# SFP.net
KiCad netlist of a schematic drawn in Altium Designer
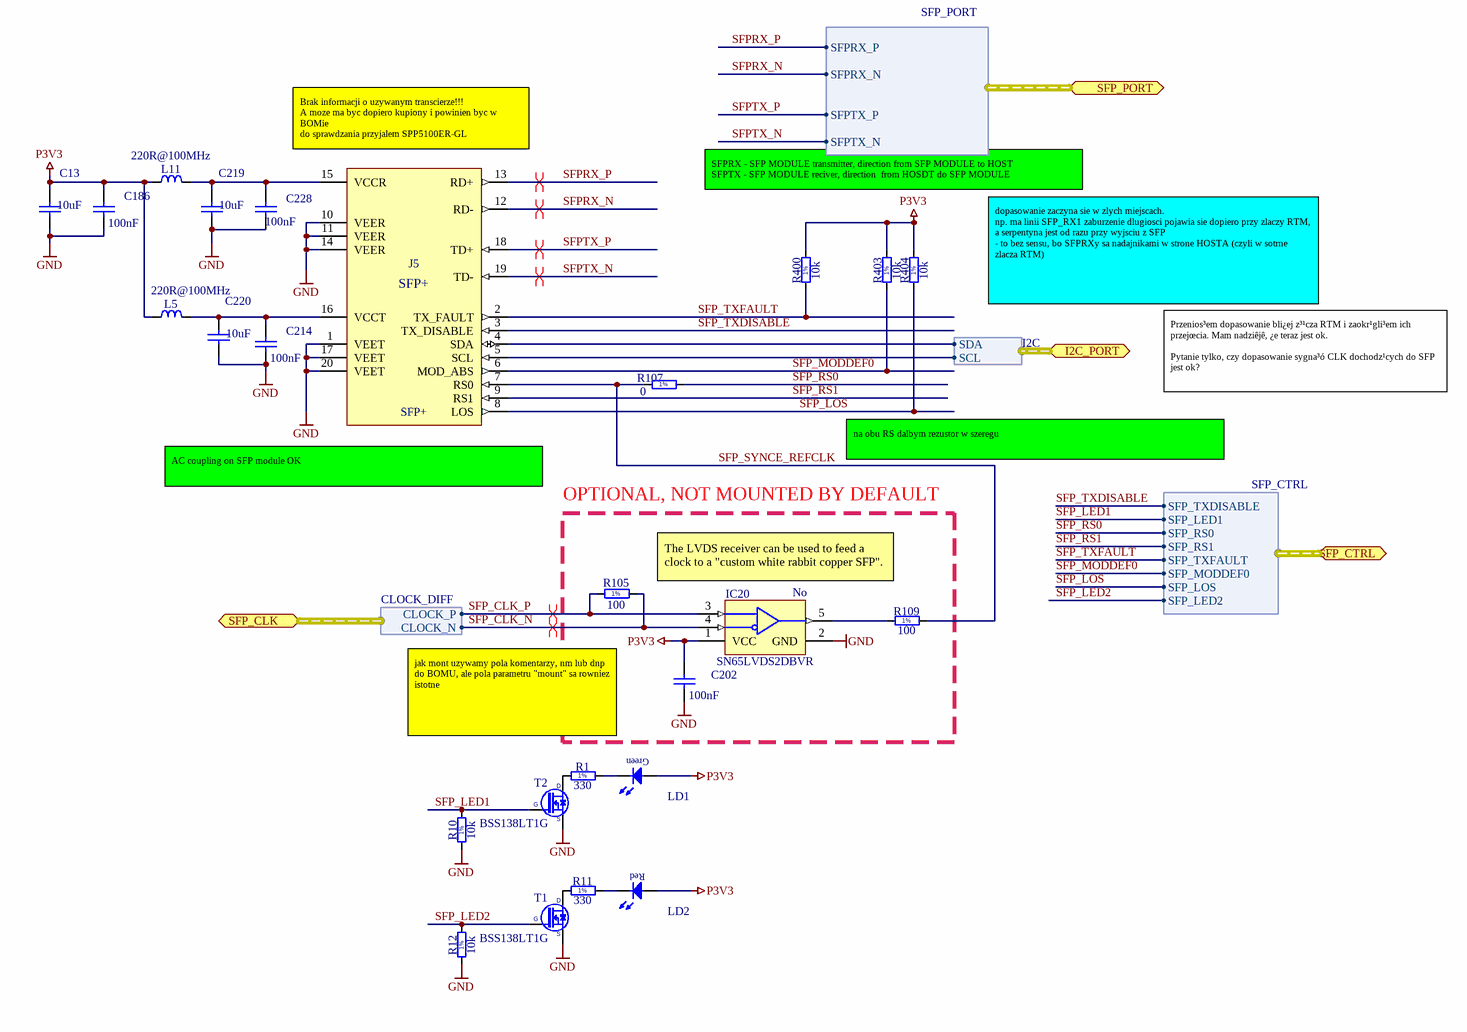
[diagram p0: SFP.SchDoc]

(export (version "E")
  (design (tool "Eeschema 10.0.6"))
  (components
    (comp (ref "C13")
      (value "10uF")
      (footprint "CAPC2012X135N")
      (description "Non-polarised capacitor")
      (fields
        (field (name "PART NUMBER") "CC0805_10UF_10V_10%_X7R")
        (field (name "VOLTAGE") "10V")
        (field (name "AUTHOR") "CERN DEM JLC")
      )
      (libsource (lib "Capacitors") (part "Capacitor - non polarized"))
    )
    (comp (ref "C186")
      (value "100nF")
      (footprint "CAPC1005X55N")
      (description "Non-polarised capacitor")
      (fields
        (field (name "PART NUMBER") "CC0402_100NF_16V_10%_X7R")
        (field (name "VOLTAGE") "16V")
        (field (name "AUTHOR") "CERN DEM JLC")
      )
      (libsource (lib "Capacitors") (part "Capacitor - non polarized"))
    )
    (comp (ref "C202")
      (value "100nF")
      (footprint "CAPC1005X55N")
      (description "Non-polarised capacitor")
      (fields
        (field (name "PART NUMBER") "CC0402_100NF_16V_10%_X7R")
        (field (name "VOLTAGE") "16V")
        (field (name "AUTHOR") "CERN DEM JLC")
      )
      (libsource (lib "Capacitors") (part "Capacitor - non polarized"))
    )
    (comp (ref "C214")
      (value "100nF")
      (footprint "CAPC1005X55N")
      (description "Non-polarised capacitor")
      (fields
        (field (name "PART NUMBER") "CC0402_100NF_16V_10%_X7R")
        (field (name "VOLTAGE") "16V")
        (field (name "AUTHOR") "CERN DEM JLC")
      )
      (libsource (lib "Capacitors") (part "Capacitor - non polarized"))
    )
    (comp (ref "C219")
      (value "10uF")
      (footprint "CAPC2012X135N")
      (description "Non-polarised capacitor")
      (fields
        (field (name "PART NUMBER") "CC0805_10UF_10V_10%_X7R")
        (field (name "VOLTAGE") "10V")
        (field (name "AUTHOR") "CERN DEM JLC")
      )
      (libsource (lib "Capacitors") (part "Capacitor - non polarized"))
    )
    (comp (ref "C220")
      (value "10uF")
      (footprint "CAPC2012X135N")
      (description "Non-polarised capacitor")
      (fields
        (field (name "PART NUMBER") "CC0805_10UF_10V_10%_X7R")
        (field (name "VOLTAGE") "10V")
        (field (name "AUTHOR") "CERN DEM JLC")
      )
      (libsource (lib "Capacitors") (part "Capacitor - non polarized"))
    )
    (comp (ref "C228")
      (value "100nF")
      (footprint "CAPC1005X55N")
      (description "Non-polarised capacitor")
      (fields
        (field (name "PART NUMBER") "CC0402_100NF_16V_10%_X7R")
        (field (name "VOLTAGE") "16V")
        (field (name "AUTHOR") "CERN DEM JLC")
      )
      (libsource (lib "Capacitors") (part "Capacitor - non polarized"))
    )
    (comp (ref "IC20")
      (value "SN65LVDS2DBVR")
      (footprint "SOT95P280X145-5N")
      (description "High-Speed Differential Line Receiver")
      (fields
        (field (name "MANUFACTURER") "TEXAS INSTRUMENTS")
        (field (name "MOUNTED") "No")
        (field (name "AUTHOR") "CERN DEM JLC")
      )
      (libsource (lib "ICs And Semiconductors") (part "SN65LVDS2DBVR"))
    )
    (comp (ref "J5")
      (value "SFP+")
      (footprint "TYCO_1888247-1")
      (description "20 Position SFP+ Connector (Small Form-factor Pluggable)")
      (fields
        (field (name "PART NUMBER") "TYCO_1888247-1")
        (field (name "MANUFACTURER") "TYCO ELECTRONICS")
        (field (name "AUTHOR") "CERN DEM JLC")
      )
      (libsource (lib "Connectors") (part "SFP+x1"))
    )
    (comp (ref "L5")
      (value "220R@100MHz")
      (footprint "INDC2012X105N")
      (description "Inductor")
      (fields
        (field (name "PART NUMBER") "IND0805_MURATA_BLM21PG221SN1D")
        (field (name "POWER") "2A")
        (field (name "AUTHOR") "CERN DEM JLC")
      )
      (libsource (lib "Inductors & Transformers") (part "Inductor"))
    )
    (comp (ref "L11")
      (value "220R@100MHz")
      (footprint "INDC2012X105N")
      (description "Inductor")
      (fields
        (field (name "PART NUMBER") "IND0805_MURATA_BLM21PG221SN1D")
        (field (name "POWER") "2A")
        (field (name "AUTHOR") "CERN DEM JLC")
      )
      (libsource (lib "Inductors & Transformers") (part "Inductor"))
    )
    (comp (ref "LD1")
      (value "Green")
      (footprint "LED_AVAGO_HSME-C120")
      (description "LED Green 1C 2A")
      (fields
        (field (name "PART NUMBER") "LED_AVAGO_HSME-C120")
        (field (name "MANUFACTURER") "AVAGO TECHNOLOGIES")
        (field (name "AUTHOR") "CERN DEM JMW")
      )
      (libsource (lib "ICs And Semiconductors") (part "LED Green 1C 2A"))
    )
    (comp (ref "LD2")
      (value "Red")
      (footprint "LED_AVAGO_HSMC-C120")
      (description "LED Red 1C 2A")
      (fields
        (field (name "PART NUMBER") "LED_AVAGO_HSMC-C120")
        (field (name "MANUFACTURER") "AVAGO TECHNOLOGIES")
        (field (name "AUTHOR") "CERN DEM JMW")
      )
      (libsource (lib "ICs And Semiconductors") (part "LED Red 1C 2A"))
    )
    (comp (ref "R1")
      (value "330")
      (footprint "RESC1608X55N")
      (description "Resistor - 1%")
      (fields
        (field (name "PART NUMBER") "R0603_330R_1%_0.1W_100PPM")
        (field (name "POWER") "0.1W")
        (field (name "AUTHOR") "CERN DEM JLC")
      )
      (libsource (lib "Resistors") (part "Resistor - 1%"))
    )
    (comp (ref "R10")
      (value "10k")
      (footprint "RESC1005X40N")
      (description "Resistor - 1%")
      (fields
        (field (name "PART NUMBER") "R0402_10K_1%_0.0625W_100PPM")
        (field (name "POWER") "0.0625W")
        (field (name "AUTHOR") "CERN DEM JLC")
      )
      (libsource (lib "Resistors") (part "Resistor - 1%"))
    )
    (comp (ref "R11")
      (value "330")
      (footprint "RESC1608X55N")
      (description "Resistor - 1%")
      (fields
        (field (name "PART NUMBER") "R0603_330R_1%_0.1W_100PPM")
        (field (name "POWER") "0.1W")
        (field (name "AUTHOR") "CERN DEM JLC")
      )
      (libsource (lib "Resistors") (part "Resistor - 1%"))
    )
    (comp (ref "R12")
      (value "10k")
      (footprint "RESC1005X40N")
      (description "Resistor - 1%")
      (fields
        (field (name "PART NUMBER") "R0402_10K_1%_0.0625W_100PPM")
        (field (name "POWER") "0.0625W")
        (field (name "AUTHOR") "CERN DEM JLC")
      )
      (libsource (lib "Resistors") (part "Resistor - 1%"))
    )
    (comp (ref "R105")
      (value "100")
      (footprint "RESC1608X55N")
      (description "Resistor - 1%")
      (fields
        (field (name "PART NUMBER") "R0603_100R_1%_0.1W_100PPM")
        (field (name "POWER") "0.1W")
        (field (name "AUTHOR") "CERN DEM JLC")
      )
      (libsource (lib "Resistors") (part "Resistor - 1%"))
    )
    (comp (ref "R107")
      (value "0")
      (footprint "RESC1608X55N")
      (description "Resistor - 1%")
      (fields
        (field (name "PART NUMBER") "R0603_0R_JUMPER")
        (field (name "MANUFACTURER") "GENERIC")
        (field (name "AUTHOR") "CERN DEM JLC")
      )
      (libsource (lib "Resistors") (part "Resistor - 1%"))
    )
    (comp (ref "R109")
      (value "100")
      (footprint "RESC1608X55N")
      (description "Resistor - 1%")
      (fields
        (field (name "PART NUMBER") "R0603_100R_1%_0.1W_100PPM")
        (field (name "POWER") "0.1W")
        (field (name "AUTHOR") "CERN DEM JLC")
      )
      (libsource (lib "Resistors") (part "Resistor - 1%"))
    )
    (comp (ref "R400")
      (value "10k")
      (footprint "RESC1005X40N")
      (description "Resistor - 1%")
      (fields
        (field (name "PART NUMBER") "R0402_10K_1%_0.0625W_100PPM")
        (field (name "POWER") "0.0625W")
        (field (name "AUTHOR") "CERN DEM JLC")
      )
      (libsource (lib "Resistors") (part "Resistor - 1%"))
    )
    (comp (ref "R403")
      (value "10k")
      (footprint "RESC1005X40N")
      (description "Resistor - 1%")
      (fields
        (field (name "PART NUMBER") "R0402_10K_1%_0.0625W_100PPM")
        (field (name "POWER") "0.0625W")
        (field (name "AUTHOR") "CERN DEM JLC")
      )
      (libsource (lib "Resistors") (part "Resistor - 1%"))
    )
    (comp (ref "R404")
      (value "10k")
      (footprint "RESC1005X40N")
      (description "Resistor - 1%")
      (fields
        (field (name "PART NUMBER") "R0402_10K_1%_0.0625W_100PPM")
        (field (name "POWER") "0.0625W")
        (field (name "AUTHOR") "CERN DEM JLC")
      )
      (libsource (lib "Resistors") (part "Resistor - 1%"))
    )
    (comp (ref "T1")
      (value "BSS138LT1G")
      (footprint "SOT95P240X110-3N")
      (description "N-CHANNEL MOSFET WITH DIODE")
      (fields (field (name "MANUFACTURER") "ON SEMICONDUCTOR") (field (name "AUTHOR") "CERN DEM JLC"))
      (libsource (lib "ICs And Semiconductors") (part "N-MOSFET-D 1G 2S 3D"))
    )
    (comp (ref "T2")
      (value "BSS138LT1G")
      (footprint "SOT95P240X110-3N")
      (description "N-CHANNEL MOSFET WITH DIODE")
      (fields (field (name "MANUFACTURER") "ON SEMICONDUCTOR") (field (name "AUTHOR") "CERN DEM JLC"))
      (libsource (lib "ICs And Semiconductors") (part "N-MOSFET-D 1G 2S 3D"))
    )
  )
  (nets
    (net (code "5") (name "/SCL") (class "Default")
      (node (ref "J5") (pin "5") (pinfunction "SCL_5") (pintype "input"))
    )
    (net (code "6") (name "/SDA") (class "Default")
      (node (ref "J5") (pin "4") (pinfunction "SDA_4") (pintype "bidirectional"))
    )
    (net (code "7") (name "/SFPRX_N") (class "Default")
      (node (ref "J5") (pin "12") (pinfunction "RD-_12") (pintype "output"))
    )
    (net (code "8") (name "/SFPRX_P") (class "Default")
      (node (ref "J5") (pin "13") (pinfunction "RD+_13") (pintype "output"))
    )
    (net (code "9") (name "/SFPTX_N") (class "Default")
      (node (ref "J5") (pin "19") (pinfunction "TD-_19") (pintype "input"))
    )
    (net (code "10") (name "/SFPTX_P") (class "Default")
      (node (ref "J5") (pin "18") (pinfunction "TD+_18") (pintype "input"))
    )
    (net (code "11") (name "/SFP_CLK_N") (class "Default")
      (node (ref "IC20") (pin "4") (pinfunction "B_4") (pintype "input"))
      (node (ref "R105") (pin "2") (pinfunction "2_2") (pintype "passive"))
    )
    (net (code "12") (name "/SFP_CLK_P") (class "Default")
      (node (ref "IC20") (pin "3") (pinfunction "A_3") (pintype "input"))
      (node (ref "R105") (pin "1") (pinfunction "1_1") (pintype "passive"))
    )
    (net (code "13") (name "/SFP_LED1") (class "Default")
      (node (ref "R10") (pin "2") (pinfunction "2_2") (pintype "passive"))
      (node (ref "T2") (pin "1") (pinfunction "G_1") (pintype "passive"))
    )
    (net (code "14") (name "/SFP_LED2") (class "Default")
      (node (ref "R12") (pin "2") (pinfunction "2_2") (pintype "passive"))
      (node (ref "T1") (pin "1") (pinfunction "G_1") (pintype "passive"))
    )
    (net (code "15") (name "/SFP_LOS") (class "Default")
      (node (ref "J5") (pin "8") (pinfunction "LOS_8") (pintype "output"))
      (node (ref "R404") (pin "1") (pinfunction "1_1") (pintype "passive"))
    )
    (net (code "16") (name "/SFP_MODDEF0") (class "Default")
      (node (ref "J5") (pin "6") (pinfunction "MOD_ABS_6") (pintype "output"))
      (node (ref "R403") (pin "1") (pinfunction "1_1") (pintype "passive"))
    )
    (net (code "17") (name "/SFP_RS0") (class "Default")
      (node (ref "R107") (pin "2") (pinfunction "2_2") (pintype "passive"))
    )
    (net (code "18") (name "/SFP_RS1") (class "Default")
      (node (ref "J5") (pin "9") (pinfunction "RS1_9") (pintype "input"))
    )
    (net (code "19") (name "/SFP_SYNCE_REFCLK") (class "Default")
      (node (ref "J5") (pin "7") (pinfunction "RS0_7") (pintype "input"))
      (node (ref "R107") (pin "1") (pinfunction "1_1") (pintype "passive"))
      (node (ref "R109") (pin "2") (pinfunction "2_2") (pintype "passive"))
    )
    (net (code "20") (name "/SFP_TXDISABLE") (class "Default")
      (node (ref "J5") (pin "3") (pinfunction "TX_DISABLE_3") (pintype "input"))
    )
    (net (code "21") (name "/SFP_TXFAULT") (class "Default")
      (node (ref "J5") (pin "2") (pinfunction "TX_FAULT_2") (pintype "output"))
      (node (ref "R400") (pin "1") (pinfunction "1_1") (pintype "passive"))
    )
    (net (code "26") (name "GND") (class "Default")
      (node (ref "C13") (pin "2") (pinfunction "2_2") (pintype "passive"))
      (node (ref "C186") (pin "2") (pinfunction "2_2") (pintype "passive"))
      (node (ref "C202") (pin "1") (pinfunction "1_1") (pintype "passive"))
      (node (ref "C214") (pin "2") (pinfunction "2_2") (pintype "passive"))
      (node (ref "C219") (pin "2") (pinfunction "2_2") (pintype "passive"))
      (node (ref "C220") (pin "2") (pinfunction "2_2") (pintype "passive"))
      (node (ref "C228") (pin "2") (pinfunction "2_2") (pintype "passive"))
      (node (ref "IC20") (pin "2") (pinfunction "GND_2") (pintype "power_in"))
      (node (ref "J5") (pin "1") (pinfunction "VEET_1") (pintype "power_in"))
      (node (ref "J5") (pin "10") (pinfunction "VEER_10") (pintype "power_in"))
      (node (ref "J5") (pin "11") (pinfunction "VEER_11") (pintype "power_in"))
      (node (ref "J5") (pin "14") (pinfunction "VEER_14") (pintype "power_in"))
      (node (ref "J5") (pin "17") (pinfunction "VEET_17") (pintype "power_in"))
      (node (ref "J5") (pin "20") (pinfunction "VEET_20") (pintype "power_in"))
      (node (ref "R10") (pin "1") (pinfunction "1_1") (pintype "passive"))
      (node (ref "R12") (pin "1") (pinfunction "1_1") (pintype "passive"))
      (node (ref "T1") (pin "2") (pinfunction "S_2") (pintype "passive"))
      (node (ref "T2") (pin "2") (pinfunction "S_2") (pintype "passive"))
    )
    (net (code "27") (name "Net-(IC20-R)") (class "Default")
      (node (ref "IC20") (pin "5") (pinfunction "R_5") (pintype "output"))
      (node (ref "R109") (pin "1") (pinfunction "1_1") (pintype "passive"))
    )
    (net (code "28") (name "Net-(J5-VCCR)") (class "Default")
      (node (ref "C219") (pin "1") (pinfunction "1_1") (pintype "passive"))
      (node (ref "C228") (pin "1") (pinfunction "1_1") (pintype "passive"))
      (node (ref "J5") (pin "15") (pinfunction "VCCR_15") (pintype "power_in"))
      (node (ref "L11") (pin "2") (pinfunction "2_2") (pintype "passive"))
    )
    (net (code "29") (name "Net-(J5-VCCT)") (class "Default")
      (node (ref "C214") (pin "1") (pinfunction "1_1") (pintype "passive"))
      (node (ref "C220") (pin "1") (pinfunction "1_1") (pintype "passive"))
      (node (ref "J5") (pin "16") (pinfunction "VCCT_16") (pintype "power_in"))
      (node (ref "L5") (pin "2") (pinfunction "2_2") (pintype "passive"))
    )
    (net (code "30") (name "Net-(LD1-C)") (class "Default")
      (node (ref "LD1") (pin "1") (pinfunction "C_1") (pintype "passive"))
      (node (ref "R1") (pin "2") (pinfunction "2_2") (pintype "passive"))
    )
    (net (code "31") (name "Net-(LD2-C)") (class "Default")
      (node (ref "LD2") (pin "1") (pinfunction "C_1") (pintype "passive"))
      (node (ref "R11") (pin "2") (pinfunction "2_2") (pintype "passive"))
    )
    (net (code "32") (name "Net-(T1-D)") (class "Default")
      (node (ref "R11") (pin "1") (pinfunction "1_1") (pintype "passive"))
      (node (ref "T1") (pin "3") (pinfunction "D_3") (pintype "passive"))
    )
    (net (code "33") (name "Net-(T2-D)") (class "Default")
      (node (ref "R1") (pin "1") (pinfunction "1_1") (pintype "passive"))
      (node (ref "T2") (pin "3") (pinfunction "D_3") (pintype "passive"))
    )
    (net (code "34") (name "P3V3") (class "Default")
      (node (ref "C13") (pin "1") (pinfunction "1_1") (pintype "passive"))
      (node (ref "C186") (pin "1") (pinfunction "1_1") (pintype "passive"))
      (node (ref "C202") (pin "2") (pinfunction "2_2") (pintype "passive"))
      (node (ref "IC20") (pin "1") (pinfunction "VCC_1") (pintype "power_in"))
      (node (ref "L11") (pin "1") (pinfunction "1_1") (pintype "passive"))
      (node (ref "L5") (pin "1") (pinfunction "1_1") (pintype "passive"))
      (node (ref "LD1") (pin "2") (pinfunction "A_2") (pintype "passive"))
      (node (ref "LD2") (pin "2") (pinfunction "A_2") (pintype "passive"))
      (node (ref "R400") (pin "2") (pinfunction "2_2") (pintype "passive"))
      (node (ref "R403") (pin "2") (pinfunction "2_2") (pintype "passive"))
      (node (ref "R404") (pin "2") (pinfunction "2_2") (pintype "passive"))
    )
  )
)
